# Final.net
KiCad netlist of a schematic drawn in EAGLE
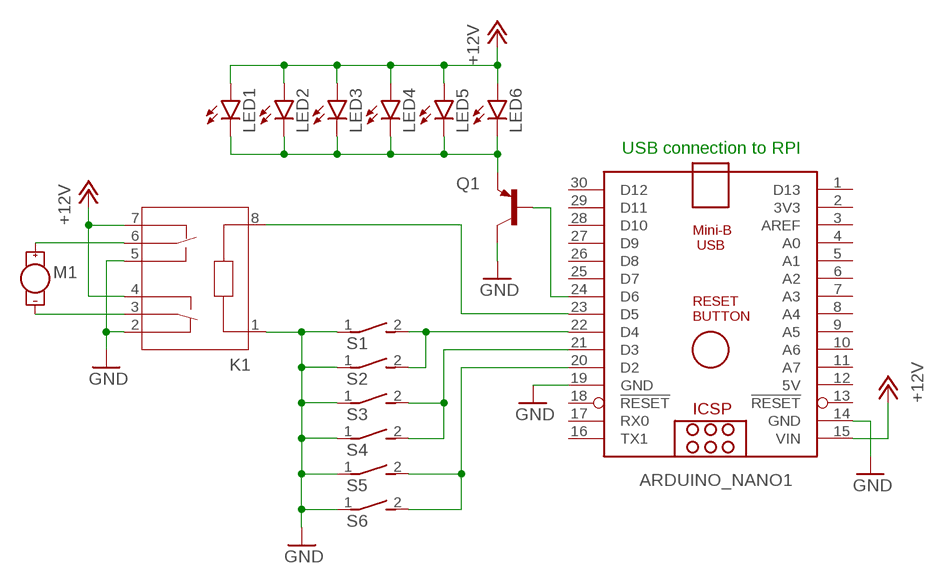
[diagram p0: schematic, sheet 1]

(export (version "E")
  (design (tool "Eeschema 10.0.6"))
  (components
    (comp (ref "ARDUINO_NANO1")
      (value "ARDUINO_NANO")
      (footprint "eagle-import:ARDUINO_NANO")
      (libsource (lib "eagle-import") (part "ARDUINO_NANO"))
    )
    (comp (ref "K1")
      (value "IM06GR")
      (footprint "eagle-import:RELAY_IM06GR")
      (fields (field (name "COMMENT") "2-1462037-3") (field (name "MF") "TE Connectivity"))
      (libsource (lib "eagle-import") (part "IM06GR"))
    )
    (comp (ref "LED1")
      (value "LAP4-BOTTOM")
      (footprint "eagle-import:P47F-BOTTOM")
      (libsource (lib "eagle-import") (part "P4-BOTTOMLA"))
    )
    (comp (ref "LED2")
      (value "LAP4-BOTTOM")
      (footprint "eagle-import:P47F-BOTTOM")
      (libsource (lib "eagle-import") (part "P4-BOTTOMLA"))
    )
    (comp (ref "LED3")
      (value "LAP4-BOTTOM")
      (footprint "eagle-import:P47F-BOTTOM")
      (libsource (lib "eagle-import") (part "P4-BOTTOMLA"))
    )
    (comp (ref "LED4")
      (value "LAP4-BOTTOM")
      (footprint "eagle-import:P47F-BOTTOM")
      (libsource (lib "eagle-import") (part "P4-BOTTOMLA"))
    )
    (comp (ref "LED5")
      (value "LAP4-BOTTOM")
      (footprint "eagle-import:P47F-BOTTOM")
      (libsource (lib "eagle-import") (part "P4-BOTTOMLA"))
    )
    (comp (ref "LED6")
      (value "LAP4-BOTTOM")
      (footprint "eagle-import:P47F-BOTTOM")
      (libsource (lib "eagle-import") (part "P4-BOTTOMLA"))
    )
    (comp (ref "M1")
      (value "MOTOR10MM")
      (footprint "eagle-import:VIBE-MOTOR-10MM")
      (libsource (lib "eagle-import") (part "MOTOR10MM"))
    )
    (comp (ref "Q1")
      (value "MMBTA56-SOT23")
      (footprint "eagle-import:SOT23")
      (libsource (lib "eagle-import") (part "-?SOT23MMBTA56"))
    )
    (comp (ref "S1")
      (value "DS01E")
      (footprint "eagle-import:DS-01")
      (libsource (lib "eagle-import") (part "DS01E"))
    )
    (comp (ref "S2")
      (value "DS01E")
      (footprint "eagle-import:DS-01")
      (libsource (lib "eagle-import") (part "DS01E"))
    )
    (comp (ref "S3")
      (value "DS01E")
      (footprint "eagle-import:DS-01")
      (libsource (lib "eagle-import") (part "DS01E"))
    )
    (comp (ref "S4")
      (value "DS01E")
      (footprint "eagle-import:DS-01")
      (libsource (lib "eagle-import") (part "DS01E"))
    )
    (comp (ref "S5")
      (value "DS01E")
      (footprint "eagle-import:DS-01")
      (libsource (lib "eagle-import") (part "DS01E"))
    )
    (comp (ref "S6")
      (value "DS01E")
      (footprint "eagle-import:DS-01")
      (libsource (lib "eagle-import") (part "DS01E"))
    )
  )
  (nets
    (net (code "1") (name "+12V") (class "Default")
      (node (ref "ARDUINO_NANO1") (pin "15") (pinfunction "VIN_15") (pintype "power_in"))
      (node (ref "K1") (pin "4") (pinfunction "4_4") (pintype "passive"))
      (node (ref "K1") (pin "7") (pinfunction "7_7") (pintype "passive"))
      (node (ref "LED1") (pin "A") (pinfunction "A_A") (pintype "passive"))
      (node (ref "LED2") (pin "A") (pinfunction "A_A") (pintype "passive"))
      (node (ref "LED3") (pin "A") (pinfunction "A_A") (pintype "passive"))
      (node (ref "LED4") (pin "A") (pinfunction "A_A") (pintype "passive"))
      (node (ref "LED5") (pin "A") (pinfunction "A_A") (pintype "passive"))
      (node (ref "LED6") (pin "A") (pinfunction "A_A") (pintype "passive"))
    )
    (net (code "2") (name "/5V") (class "Default")
      (node (ref "ARDUINO_NANO1") (pin "12") (pinfunction "5V_12") (pintype "power_in"))
    )
    (net (code "3") (name "GND") (class "Default")
      (node (ref "ARDUINO_NANO1") (pin "14") (pinfunction "GND_14") (pintype "power_in"))
      (node (ref "ARDUINO_NANO1") (pin "19") (pinfunction "GND_19") (pintype "power_in"))
      (node (ref "K1") (pin "1") (pinfunction "1_1") (pintype "passive"))
      (node (ref "K1") (pin "2") (pinfunction "2_2") (pintype "passive"))
      (node (ref "K1") (pin "5") (pinfunction "5_5") (pintype "passive"))
      (node (ref "Q1") (pin "3") (pinfunction "C_3") (pintype "passive"))
      (node (ref "S1") (pin "1") (pinfunction "1_1") (pintype "passive"))
      (node (ref "S2") (pin "1") (pinfunction "1_1") (pintype "passive"))
      (node (ref "S3") (pin "1") (pinfunction "1_1") (pintype "passive"))
      (node (ref "S4") (pin "1") (pinfunction "1_1") (pintype "passive"))
      (node (ref "S5") (pin "1") (pinfunction "1_1") (pintype "passive"))
      (node (ref "S6") (pin "1") (pinfunction "1_1") (pintype "passive"))
    )
    (net (code "4") (name "Net-(ARDUINO_NANO1-D2)") (class "Default")
      (node (ref "ARDUINO_NANO1") (pin "20") (pinfunction "D2_20") (pintype "bidirectional"))
      (node (ref "S5") (pin "2") (pinfunction "2_2") (pintype "passive"))
      (node (ref "S6") (pin "2") (pinfunction "2_2") (pintype "passive"))
    )
    (net (code "5") (name "Net-(ARDUINO_NANO1-D3)") (class "Default")
      (node (ref "ARDUINO_NANO1") (pin "21") (pinfunction "D3_21") (pintype "bidirectional"))
      (node (ref "S3") (pin "2") (pinfunction "2_2") (pintype "passive"))
      (node (ref "S4") (pin "2") (pinfunction "2_2") (pintype "passive"))
    )
    (net (code "6") (name "Net-(ARDUINO_NANO1-D4)") (class "Default")
      (node (ref "ARDUINO_NANO1") (pin "22") (pinfunction "D4_22") (pintype "bidirectional"))
      (node (ref "S1") (pin "2") (pinfunction "2_2") (pintype "passive"))
      (node (ref "S2") (pin "2") (pinfunction "2_2") (pintype "passive"))
    )
    (net (code "7") (name "Net-(ARDUINO_NANO1-D5)") (class "Default")
      (node (ref "ARDUINO_NANO1") (pin "23") (pinfunction "D5_23") (pintype "bidirectional"))
      (node (ref "K1") (pin "8") (pinfunction "8_8") (pintype "passive"))
    )
    (net (code "8") (name "Net-(ARDUINO_NANO1-D6)") (class "Default")
      (node (ref "ARDUINO_NANO1") (pin "24") (pinfunction "D6_24") (pintype "bidirectional"))
      (node (ref "Q1") (pin "1") (pinfunction "B_1") (pintype "passive"))
    )
    (net (code "9") (name "Net-(K1-Pad3)") (class "Default")
      (node (ref "K1") (pin "3") (pinfunction "3_3") (pintype "passive"))
      (node (ref "M1") (pin "-") (pinfunction "-_-") (pintype "bidirectional"))
    )
    (net (code "10") (name "Net-(K1-Pad6)") (class "Default")
      (node (ref "K1") (pin "6") (pinfunction "6_6") (pintype "passive"))
      (node (ref "M1") (pin "+") (pinfunction "+_+") (pintype "bidirectional"))
    )
    (net (code "11") (name "Net-(Q1-E)") (class "Default")
      (node (ref "LED1") (pin "C") (pinfunction "C_C") (pintype "passive"))
      (node (ref "LED2") (pin "C") (pinfunction "C_C") (pintype "passive"))
      (node (ref "LED3") (pin "C") (pinfunction "C_C") (pintype "passive"))
      (node (ref "LED4") (pin "C") (pinfunction "C_C") (pintype "passive"))
      (node (ref "LED5") (pin "C") (pinfunction "C_C") (pintype "passive"))
      (node (ref "LED6") (pin "C") (pinfunction "C_C") (pintype "passive"))
      (node (ref "Q1") (pin "2") (pinfunction "E_2") (pintype "passive"))
    )
    (net (code "12") (name "unconnected-(ARDUINO_NANO1-3V3-Pad2)") (class "Default")
      (node (ref "ARDUINO_NANO1") (pin "2") (pinfunction "3V3_2") (pintype "output"))
    )
    (net (code "13") (name "unconnected-(ARDUINO_NANO1-A0-Pad4)") (class "Default")
      (node (ref "ARDUINO_NANO1") (pin "4") (pinfunction "A0_4") (pintype "bidirectional"))
    )
    (net (code "14") (name "unconnected-(ARDUINO_NANO1-A1-Pad5)") (class "Default")
      (node (ref "ARDUINO_NANO1") (pin "5") (pinfunction "A1_5") (pintype "bidirectional"))
    )
    (net (code "15") (name "unconnected-(ARDUINO_NANO1-A2-Pad6)") (class "Default")
      (node (ref "ARDUINO_NANO1") (pin "6") (pinfunction "A2_6") (pintype "bidirectional"))
    )
    (net (code "16") (name "unconnected-(ARDUINO_NANO1-A3-Pad7)") (class "Default")
      (node (ref "ARDUINO_NANO1") (pin "7") (pinfunction "A3_7") (pintype "bidirectional"))
    )
    (net (code "17") (name "unconnected-(ARDUINO_NANO1-A4-Pad8)") (class "Default")
      (node (ref "ARDUINO_NANO1") (pin "8") (pinfunction "A4_8") (pintype "bidirectional"))
    )
    (net (code "18") (name "unconnected-(ARDUINO_NANO1-A5-Pad9)") (class "Default")
      (node (ref "ARDUINO_NANO1") (pin "9") (pinfunction "A5_9") (pintype "bidirectional"))
    )
    (net (code "19") (name "unconnected-(ARDUINO_NANO1-A6-Pad10)") (class "Default")
      (node (ref "ARDUINO_NANO1") (pin "10") (pinfunction "A6_10") (pintype "bidirectional"))
    )
    (net (code "20") (name "unconnected-(ARDUINO_NANO1-A7-Pad11)") (class "Default")
      (node (ref "ARDUINO_NANO1") (pin "11") (pinfunction "A7_11") (pintype "bidirectional"))
    )
    (net (code "21") (name "unconnected-(ARDUINO_NANO1-AREF-Pad3)") (class "Default")
      (node (ref "ARDUINO_NANO1") (pin "3") (pinfunction "AREF_3") (pintype "input"))
    )
    (net (code "22") (name "unconnected-(ARDUINO_NANO1-D7-Pad25)") (class "Default")
      (node (ref "ARDUINO_NANO1") (pin "25") (pinfunction "D7_25") (pintype "bidirectional"))
    )
    (net (code "23") (name "unconnected-(ARDUINO_NANO1-D8-Pad26)") (class "Default")
      (node (ref "ARDUINO_NANO1") (pin "26") (pinfunction "D8_26") (pintype "bidirectional"))
    )
    (net (code "24") (name "unconnected-(ARDUINO_NANO1-D9-Pad27)") (class "Default")
      (node (ref "ARDUINO_NANO1") (pin "27") (pinfunction "D9_27") (pintype "bidirectional"))
    )
    (net (code "25") (name "unconnected-(ARDUINO_NANO1-D10-Pad28)") (class "Default")
      (node (ref "ARDUINO_NANO1") (pin "28") (pinfunction "D10_28") (pintype "bidirectional"))
    )
    (net (code "26") (name "unconnected-(ARDUINO_NANO1-D11-Pad29)") (class "Default")
      (node (ref "ARDUINO_NANO1") (pin "29") (pinfunction "D11_29") (pintype "bidirectional"))
    )
    (net (code "27") (name "unconnected-(ARDUINO_NANO1-D12-Pad30)") (class "Default")
      (node (ref "ARDUINO_NANO1") (pin "30") (pinfunction "D12_30") (pintype "bidirectional"))
    )
    (net (code "28") (name "unconnected-(ARDUINO_NANO1-D13-Pad1)") (class "Default")
      (node (ref "ARDUINO_NANO1") (pin "1") (pinfunction "D13_1") (pintype "bidirectional"))
    )
    (net (code "29") (name "unconnected-(ARDUINO_NANO1-RX0-Pad17)") (class "Default")
      (node (ref "ARDUINO_NANO1") (pin "17") (pinfunction "RX0_17") (pintype "bidirectional"))
    )
    (net (code "30") (name "unconnected-(ARDUINO_NANO1-TX1-Pad16)") (class "Default")
      (node (ref "ARDUINO_NANO1") (pin "16") (pinfunction "TX1_16") (pintype "bidirectional"))
    )
    (net (code "31") (name "unconnected-(ARDUINO_NANO1-~{RESET}-Pad13)") (class "Default")
      (node (ref "ARDUINO_NANO1") (pin "13") (pinfunction "~{RESET}_13") (pintype "input"))
    )
    (net (code "32") (name "unconnected-(ARDUINO_NANO1-~{RESET}-Pad18)") (class "Default")
      (node (ref "ARDUINO_NANO1") (pin "18") (pinfunction "~{RESET}_18") (pintype "input"))
    )
  )
)
